# Touch_Menu_Board.net
KiCad netlist of a schematic drawn in EAGLE
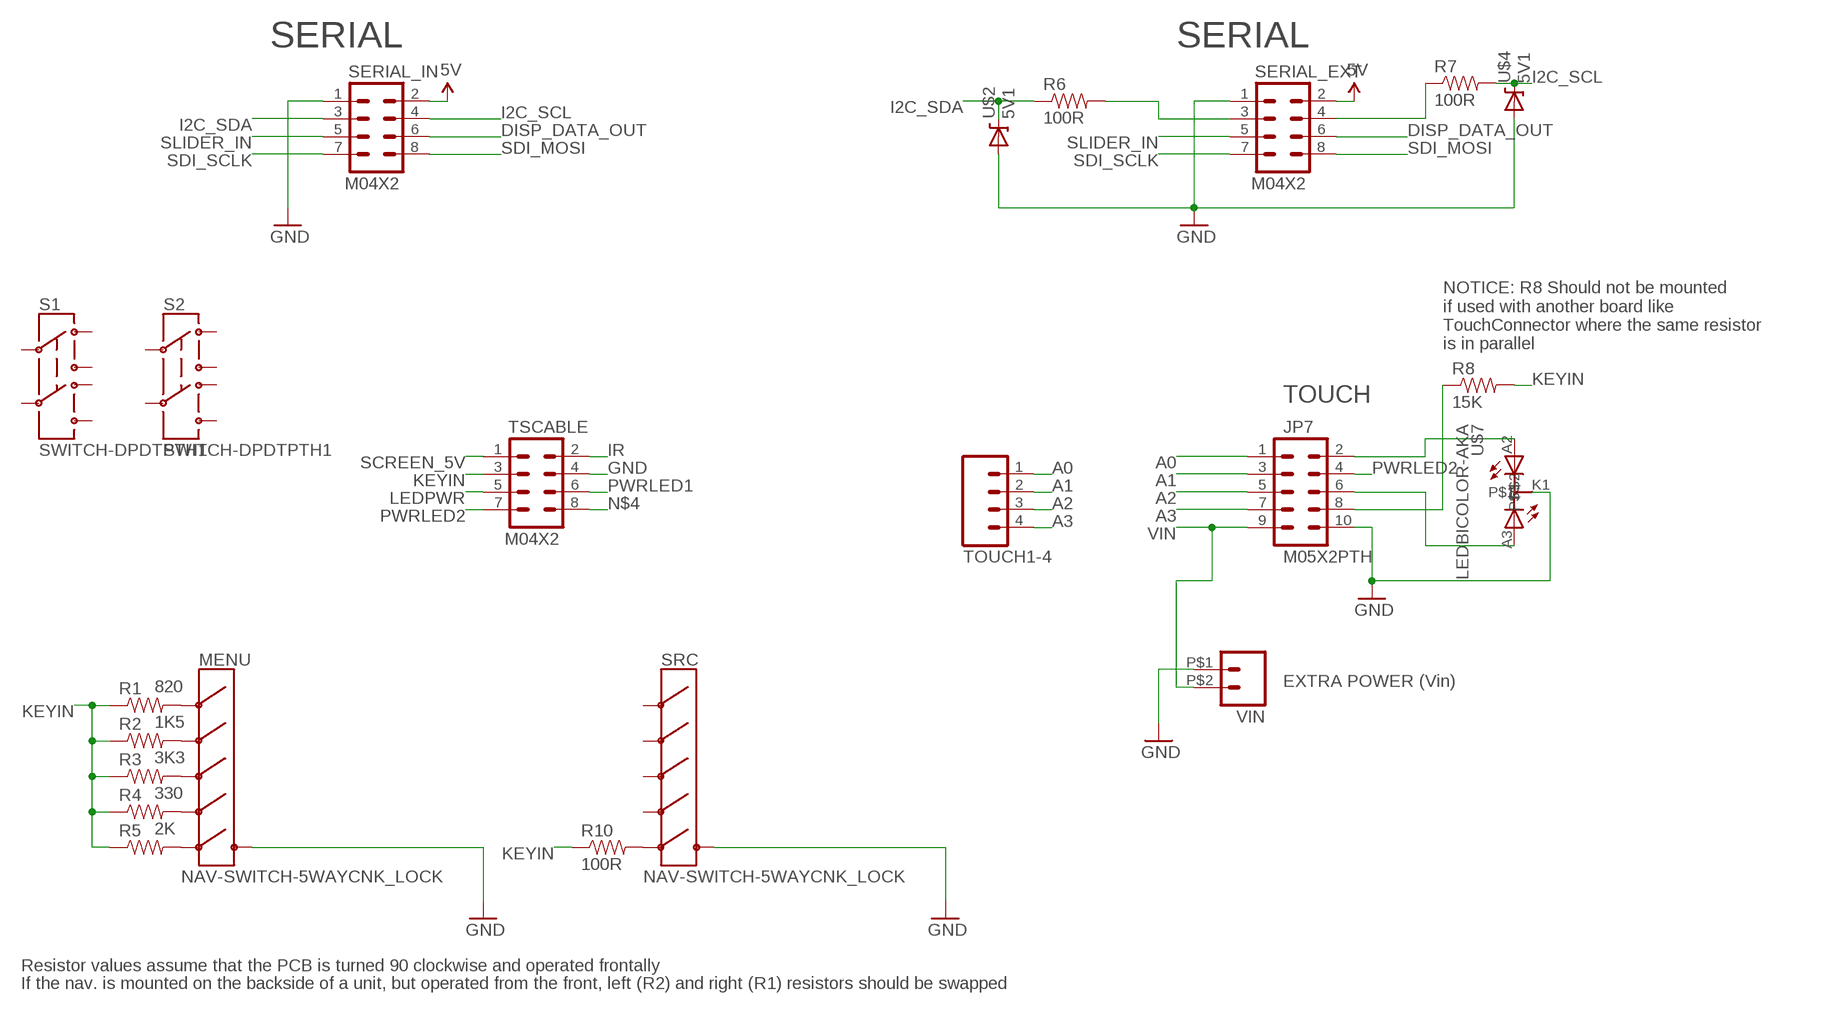
[diagram p0: schematic, sheet 1]

(export (version "E")
  (design (tool "Eeschema 10.0.6"))
  (components
    (comp (ref "JP7")
      (value "M05X2PTH")
      (footprint "eagle-import:AVR_ICSP")
      (libsource (lib "eagle-import") (part "M05X2PTH"))
    )
    (comp (ref "MENU")
      (value "NAV-SWITCH-5WAYCNK_LOCK")
      (footprint "eagle-import:NAV-SWITCH-5WAY")
      (libsource (lib "eagle-import") (part "NAV-SWITCH-5WAYCNK_LOCK"))
    )
    (comp (ref "R1")
      (value "820")
      (footprint "eagle-import:0603-RES")
      (libsource (lib "eagle-import") (part "RESISTOR0603-RES"))
    )
    (comp (ref "R2")
      (value "1K5")
      (footprint "eagle-import:0603-RES")
      (libsource (lib "eagle-import") (part "RESISTOR0603-RES"))
    )
    (comp (ref "R3")
      (value "3K3")
      (footprint "eagle-import:0603-RES")
      (libsource (lib "eagle-import") (part "RESISTOR0603-RES"))
    )
    (comp (ref "R4")
      (value "330")
      (footprint "eagle-import:0603-RES")
      (libsource (lib "eagle-import") (part "RESISTOR0603-RES"))
    )
    (comp (ref "R5")
      (value "2K")
      (footprint "eagle-import:0603-RES")
      (libsource (lib "eagle-import") (part "RESISTOR0603-RES"))
    )
    (comp (ref "R6")
      (value "100R")
      (footprint "eagle-import:0603-RES")
      (libsource (lib "eagle-import") (part "RESISTOR0603-RES"))
    )
    (comp (ref "R7")
      (value "100R")
      (footprint "eagle-import:0603-RES")
      (libsource (lib "eagle-import") (part "RESISTOR0603-RES"))
    )
    (comp (ref "R8")
      (value "15K")
      (footprint "eagle-import:0603-RES")
      (libsource (lib "eagle-import") (part "RESISTOR0603-RES"))
    )
    (comp (ref "R10")
      (value "100R")
      (footprint "eagle-import:0603-RES")
      (libsource (lib "eagle-import") (part "RESISTOR0603-RES"))
    )
    (comp (ref "S1")
      (value "SWITCH-DPDTPTH1")
      (footprint "eagle-import:TECONNECTIVITY-DPDT")
      (libsource (lib "eagle-import") (part "SWITCH-DPDTPTH1"))
    )
    (comp (ref "S2")
      (value "SWITCH-DPDTPTH1")
      (footprint "eagle-import:TECONNECTIVITY-DPDT")
      (libsource (lib "eagle-import") (part "SWITCH-DPDTPTH1"))
    )
    (comp (ref "SERIAL_EXT")
      (value "M04X2")
      (footprint "eagle-import:2X4")
      (libsource (lib "eagle-import") (part "M04X2"))
    )
    (comp (ref "SERIAL_IN")
      (value "M04X2")
      (footprint "eagle-import:2X4")
      (libsource (lib "eagle-import") (part "M04X2"))
    )
    (comp (ref "SRC")
      (value "NAV-SWITCH-5WAYCNK_LOCK")
      (footprint "eagle-import:NAV-SWITCH-5WAY")
      (libsource (lib "eagle-import") (part "NAV-SWITCH-5WAYCNK_LOCK"))
    )
    (comp (ref "TOUCH1-4")
      (value "M04PTH")
      (footprint "eagle-import:1X04")
      (libsource (lib "eagle-import") (part "M04PTH"))
    )
    (comp (ref "TSCABLE")
      (value "M04X2")
      (footprint "eagle-import:2X4")
      (libsource (lib "eagle-import") (part "M04X2"))
    )
    (comp (ref "U$2")
      (value "5V1")
      (footprint "eagle-import:DIODE-ZENER")
      (libsource (lib "eagle-import") (part "DIODE-ZENERPTH"))
    )
    (comp (ref "U$4")
      (value "5V1")
      (footprint "eagle-import:DIODE-ZENER")
      (libsource (lib "eagle-import") (part "DIODE-ZENERPTH"))
    )
    (comp (ref "U$7")
      (value "LEDBICOLOR-AKA")
      (footprint "eagle-import:LED5MM-BICOLOR")
      (libsource (lib "eagle-import") (part "LEDBICOLOR-AKA"))
    )
    (comp (ref "VIN")
      (value "M02PTH2")
      (footprint "eagle-import:1X02_BIG")
      (libsource (lib "eagle-import") (part "M02PTH2"))
    )
  )
  (nets
    (net (code "1") (name "/A0") (class "Default")
      (node (ref "JP7") (pin "1") (pinfunction "1_1") (pintype "passive"))
      (node (ref "TOUCH1-4") (pin "1") (pinfunction "1_1") (pintype "passive"))
    )
    (net (code "2") (name "/A1") (class "Default")
      (node (ref "JP7") (pin "3") (pinfunction "3_3") (pintype "passive"))
      (node (ref "TOUCH1-4") (pin "2") (pinfunction "2_2") (pintype "passive"))
    )
    (net (code "3") (name "/A2") (class "Default")
      (node (ref "JP7") (pin "5") (pinfunction "5_5") (pintype "passive"))
      (node (ref "TOUCH1-4") (pin "3") (pinfunction "3_3") (pintype "passive"))
    )
    (net (code "4") (name "/A3") (class "Default")
      (node (ref "JP7") (pin "7") (pinfunction "7_7") (pintype "passive"))
      (node (ref "TOUCH1-4") (pin "4") (pinfunction "4_4") (pintype "passive"))
    )
    (net (code "5") (name "/DISP_DATA_OUT") (class "Default")
      (node (ref "SERIAL_EXT") (pin "6") (pinfunction "6_6") (pintype "passive"))
      (node (ref "SERIAL_IN") (pin "6") (pinfunction "6_6") (pintype "passive"))
    )
    (net (code "6") (name "/I2C_SCL") (class "Default")
      (node (ref "R7") (pin "2") (pinfunction "2_2") (pintype "passive"))
      (node (ref "SERIAL_IN") (pin "4") (pinfunction "4_4") (pintype "passive"))
      (node (ref "U$4") (pin "P$1") (pinfunction "C_P$1") (pintype "passive"))
    )
    (net (code "7") (name "/I2C_SDA") (class "Default")
      (node (ref "R6") (pin "1") (pinfunction "1_1") (pintype "passive"))
      (node (ref "SERIAL_IN") (pin "3") (pinfunction "3_3") (pintype "passive"))
      (node (ref "U$2") (pin "P$1") (pinfunction "C_P$1") (pintype "passive"))
    )
    (net (code "8") (name "/IR") (class "Default")
      (node (ref "TSCABLE") (pin "2") (pinfunction "2_2") (pintype "passive"))
    )
    (net (code "9") (name "/KEYIN") (class "Default")
      (node (ref "R1") (pin "1") (pinfunction "1_1") (pintype "passive"))
      (node (ref "R10") (pin "1") (pinfunction "1_1") (pintype "passive"))
      (node (ref "R2") (pin "1") (pinfunction "1_1") (pintype "passive"))
      (node (ref "R3") (pin "1") (pinfunction "1_1") (pintype "passive"))
      (node (ref "R4") (pin "1") (pinfunction "1_1") (pintype "passive"))
      (node (ref "R5") (pin "1") (pinfunction "1_1") (pintype "passive"))
      (node (ref "R8") (pin "2") (pinfunction "2_2") (pintype "passive"))
      (node (ref "TSCABLE") (pin "3") (pinfunction "3_3") (pintype "passive"))
    )
    (net (code "10") (name "/LEDPWR") (class "Default")
      (node (ref "TSCABLE") (pin "5") (pinfunction "5_5") (pintype "passive"))
    )
    (net (code "11") (name "/N$4") (class "Default")
      (node (ref "TSCABLE") (pin "8") (pinfunction "8_8") (pintype "passive"))
    )
    (net (code "12") (name "/PWRLED1") (class "Default")
      (node (ref "TSCABLE") (pin "6") (pinfunction "6_6") (pintype "passive"))
    )
    (net (code "13") (name "/PWRLED2") (class "Default")
      (node (ref "JP7") (pin "4") (pinfunction "4_4") (pintype "passive"))
      (node (ref "TSCABLE") (pin "7") (pinfunction "7_7") (pintype "passive"))
    )
    (net (code "14") (name "/SCREEN_5V") (class "Default")
      (node (ref "TSCABLE") (pin "1") (pinfunction "1_1") (pintype "passive"))
    )
    (net (code "15") (name "/SDI_MOSI") (class "Default")
      (node (ref "SERIAL_EXT") (pin "8") (pinfunction "8_8") (pintype "passive"))
      (node (ref "SERIAL_IN") (pin "8") (pinfunction "8_8") (pintype "passive"))
    )
    (net (code "16") (name "/SDI_SCLK") (class "Default")
      (node (ref "SERIAL_EXT") (pin "7") (pinfunction "7_7") (pintype "passive"))
      (node (ref "SERIAL_IN") (pin "7") (pinfunction "7_7") (pintype "passive"))
    )
    (net (code "17") (name "/SLIDER_IN") (class "Default")
      (node (ref "SERIAL_EXT") (pin "5") (pinfunction "5_5") (pintype "passive"))
      (node (ref "SERIAL_IN") (pin "5") (pinfunction "5_5") (pintype "passive"))
    )
    (net (code "18") (name "/VIN") (class "Default")
      (node (ref "JP7") (pin "9") (pinfunction "9_9") (pintype "passive"))
      (node (ref "VIN") (pin "P$2") (pinfunction "2_P$2") (pintype "passive"))
    )
    (net (code "19") (name "5V") (class "Default")
      (node (ref "SERIAL_EXT") (pin "2") (pinfunction "2_2") (pintype "passive"))
      (node (ref "SERIAL_IN") (pin "2") (pinfunction "2_2") (pintype "passive"))
    )
    (net (code "20") (name "GND") (class "Default")
      (node (ref "JP7") (pin "10") (pinfunction "10_10") (pintype "passive"))
      (node (ref "MENU") (pin "PIN4") (pinfunction "COMMON_PIN4") (pintype "bidirectional"))
      (node (ref "SERIAL_EXT") (pin "1") (pinfunction "1_1") (pintype "passive"))
      (node (ref "SERIAL_IN") (pin "1") (pinfunction "1_1") (pintype "passive"))
      (node (ref "SRC") (pin "PIN4") (pinfunction "COMMON_PIN4") (pintype "bidirectional"))
      (node (ref "TSCABLE") (pin "4") (pinfunction "4_4") (pintype "passive"))
      (node (ref "U$2") (pin "P$2") (pinfunction "A_P$2") (pintype "passive"))
      (node (ref "U$4") (pin "P$2") (pinfunction "A_P$2") (pintype "passive"))
      (node (ref "U$7") (pin "K1") (pinfunction "P$1_K1") (pintype "bidirectional"))
      (node (ref "VIN") (pin "P$1") (pinfunction "1_P$1") (pintype "passive"))
    )
    (net (code "21") (name "Net-(JP7-Pad8)") (class "Default")
      (node (ref "JP7") (pin "8") (pinfunction "8_8") (pintype "passive"))
      (node (ref "R8") (pin "1") (pinfunction "1_1") (pintype "passive"))
    )
    (net (code "22") (name "Net-(MENU-DWN)") (class "Default")
      (node (ref "MENU") (pin "PIN3") (pinfunction "DWN_PIN3") (pintype "bidirectional"))
      (node (ref "R2") (pin "2") (pinfunction "2_2") (pintype "passive"))
    )
    (net (code "23") (name "Net-(MENU-LEFT)") (class "Default")
      (node (ref "MENU") (pin "PIN2") (pinfunction "LEFT_PIN2") (pintype "bidirectional"))
      (node (ref "R3") (pin "2") (pinfunction "2_2") (pintype "passive"))
    )
    (net (code "24") (name "Net-(MENU-PUSH)") (class "Default")
      (node (ref "MENU") (pin "PIN6") (pinfunction "PUSH_PIN6") (pintype "bidirectional"))
      (node (ref "R5") (pin "2") (pinfunction "2_2") (pintype "passive"))
    )
    (net (code "25") (name "Net-(MENU-RIGHT)") (class "Default")
      (node (ref "MENU") (pin "PIN5") (pinfunction "RIGHT_PIN5") (pintype "bidirectional"))
      (node (ref "R4") (pin "2") (pinfunction "2_2") (pintype "passive"))
    )
    (net (code "26") (name "Net-(MENU-UP)") (class "Default")
      (node (ref "MENU") (pin "PIN1") (pinfunction "UP_PIN1") (pintype "bidirectional"))
      (node (ref "R1") (pin "2") (pinfunction "2_2") (pintype "passive"))
    )
    (net (code "27") (name "Net-(R6-Pad2)") (class "Default")
      (node (ref "R6") (pin "2") (pinfunction "2_2") (pintype "passive"))
      (node (ref "SERIAL_EXT") (pin "3") (pinfunction "3_3") (pintype "passive"))
    )
    (net (code "28") (name "Net-(R7-Pad1)") (class "Default")
      (node (ref "R7") (pin "1") (pinfunction "1_1") (pintype "passive"))
      (node (ref "SERIAL_EXT") (pin "4") (pinfunction "4_4") (pintype "passive"))
    )
    (net (code "29") (name "Net-(SRC-PUSH)") (class "Default")
      (node (ref "R10") (pin "2") (pinfunction "2_2") (pintype "passive"))
      (node (ref "SRC") (pin "PIN6") (pinfunction "PUSH_PIN6") (pintype "bidirectional"))
    )
    (net (code "30") (name "Net-(U$7-P$2)") (class "Default")
      (node (ref "JP7") (pin "2") (pinfunction "2_2") (pintype "passive"))
      (node (ref "U$7") (pin "A2") (pinfunction "P$2_A2") (pintype "bidirectional"))
    )
    (net (code "31") (name "Net-(U$7-P$3)") (class "Default")
      (node (ref "JP7") (pin "6") (pinfunction "6_6") (pintype "passive"))
      (node (ref "U$7") (pin "A3") (pinfunction "P$3_A3") (pintype "bidirectional"))
    )
    (net (code "32") (name "unconnected-(S1-1-PadP$1)") (class "Default")
      (node (ref "S1") (pin "P$1") (pinfunction "1_P$1") (pintype "bidirectional"))
    )
    (net (code "33") (name "unconnected-(S1-2-PadP$2)") (class "Default")
      (node (ref "S1") (pin "P$2") (pinfunction "2_P$2") (pintype "bidirectional"))
    )
    (net (code "34") (name "unconnected-(S1-3-PadP$3)") (class "Default")
      (node (ref "S1") (pin "P$3") (pinfunction "3_P$3") (pintype "bidirectional"))
    )
    (net (code "35") (name "unconnected-(S1-4-PadP$4)") (class "Default")
      (node (ref "S1") (pin "P$4") (pinfunction "4_P$4") (pintype "bidirectional"))
    )
    (net (code "36") (name "unconnected-(S1-5-PadP$5)") (class "Default")
      (node (ref "S1") (pin "P$5") (pinfunction "5_P$5") (pintype "bidirectional"))
    )
    (net (code "37") (name "unconnected-(S1-6-PadP$6)") (class "Default")
      (node (ref "S1") (pin "P$6") (pinfunction "6_P$6") (pintype "bidirectional"))
    )
    (net (code "38") (name "unconnected-(S2-1-PadP$1)") (class "Default")
      (node (ref "S2") (pin "P$1") (pinfunction "1_P$1") (pintype "bidirectional"))
    )
    (net (code "39") (name "unconnected-(S2-2-PadP$2)") (class "Default")
      (node (ref "S2") (pin "P$2") (pinfunction "2_P$2") (pintype "bidirectional"))
    )
    (net (code "40") (name "unconnected-(S2-3-PadP$3)") (class "Default")
      (node (ref "S2") (pin "P$3") (pinfunction "3_P$3") (pintype "bidirectional"))
    )
    (net (code "41") (name "unconnected-(S2-4-PadP$4)") (class "Default")
      (node (ref "S2") (pin "P$4") (pinfunction "4_P$4") (pintype "bidirectional"))
    )
    (net (code "42") (name "unconnected-(S2-5-PadP$5)") (class "Default")
      (node (ref "S2") (pin "P$5") (pinfunction "5_P$5") (pintype "bidirectional"))
    )
    (net (code "43") (name "unconnected-(S2-6-PadP$6)") (class "Default")
      (node (ref "S2") (pin "P$6") (pinfunction "6_P$6") (pintype "bidirectional"))
    )
    (net (code "44") (name "unconnected-(SRC-DWN-PadPIN3)") (class "Default")
      (node (ref "SRC") (pin "PIN3") (pinfunction "DWN_PIN3") (pintype "bidirectional"))
    )
    (net (code "45") (name "unconnected-(SRC-LEFT-PadPIN2)") (class "Default")
      (node (ref "SRC") (pin "PIN2") (pinfunction "LEFT_PIN2") (pintype "bidirectional"))
    )
    (net (code "46") (name "unconnected-(SRC-RIGHT-PadPIN5)") (class "Default")
      (node (ref "SRC") (pin "PIN5") (pinfunction "RIGHT_PIN5") (pintype "bidirectional"))
    )
    (net (code "47") (name "unconnected-(SRC-UP-PadPIN1)") (class "Default")
      (node (ref "SRC") (pin "PIN1") (pinfunction "UP_PIN1") (pintype "bidirectional"))
    )
  )
)
